# Supplemental_Power_Switch_System.net
KiCad netlist of a schematic drawn in EAGLE
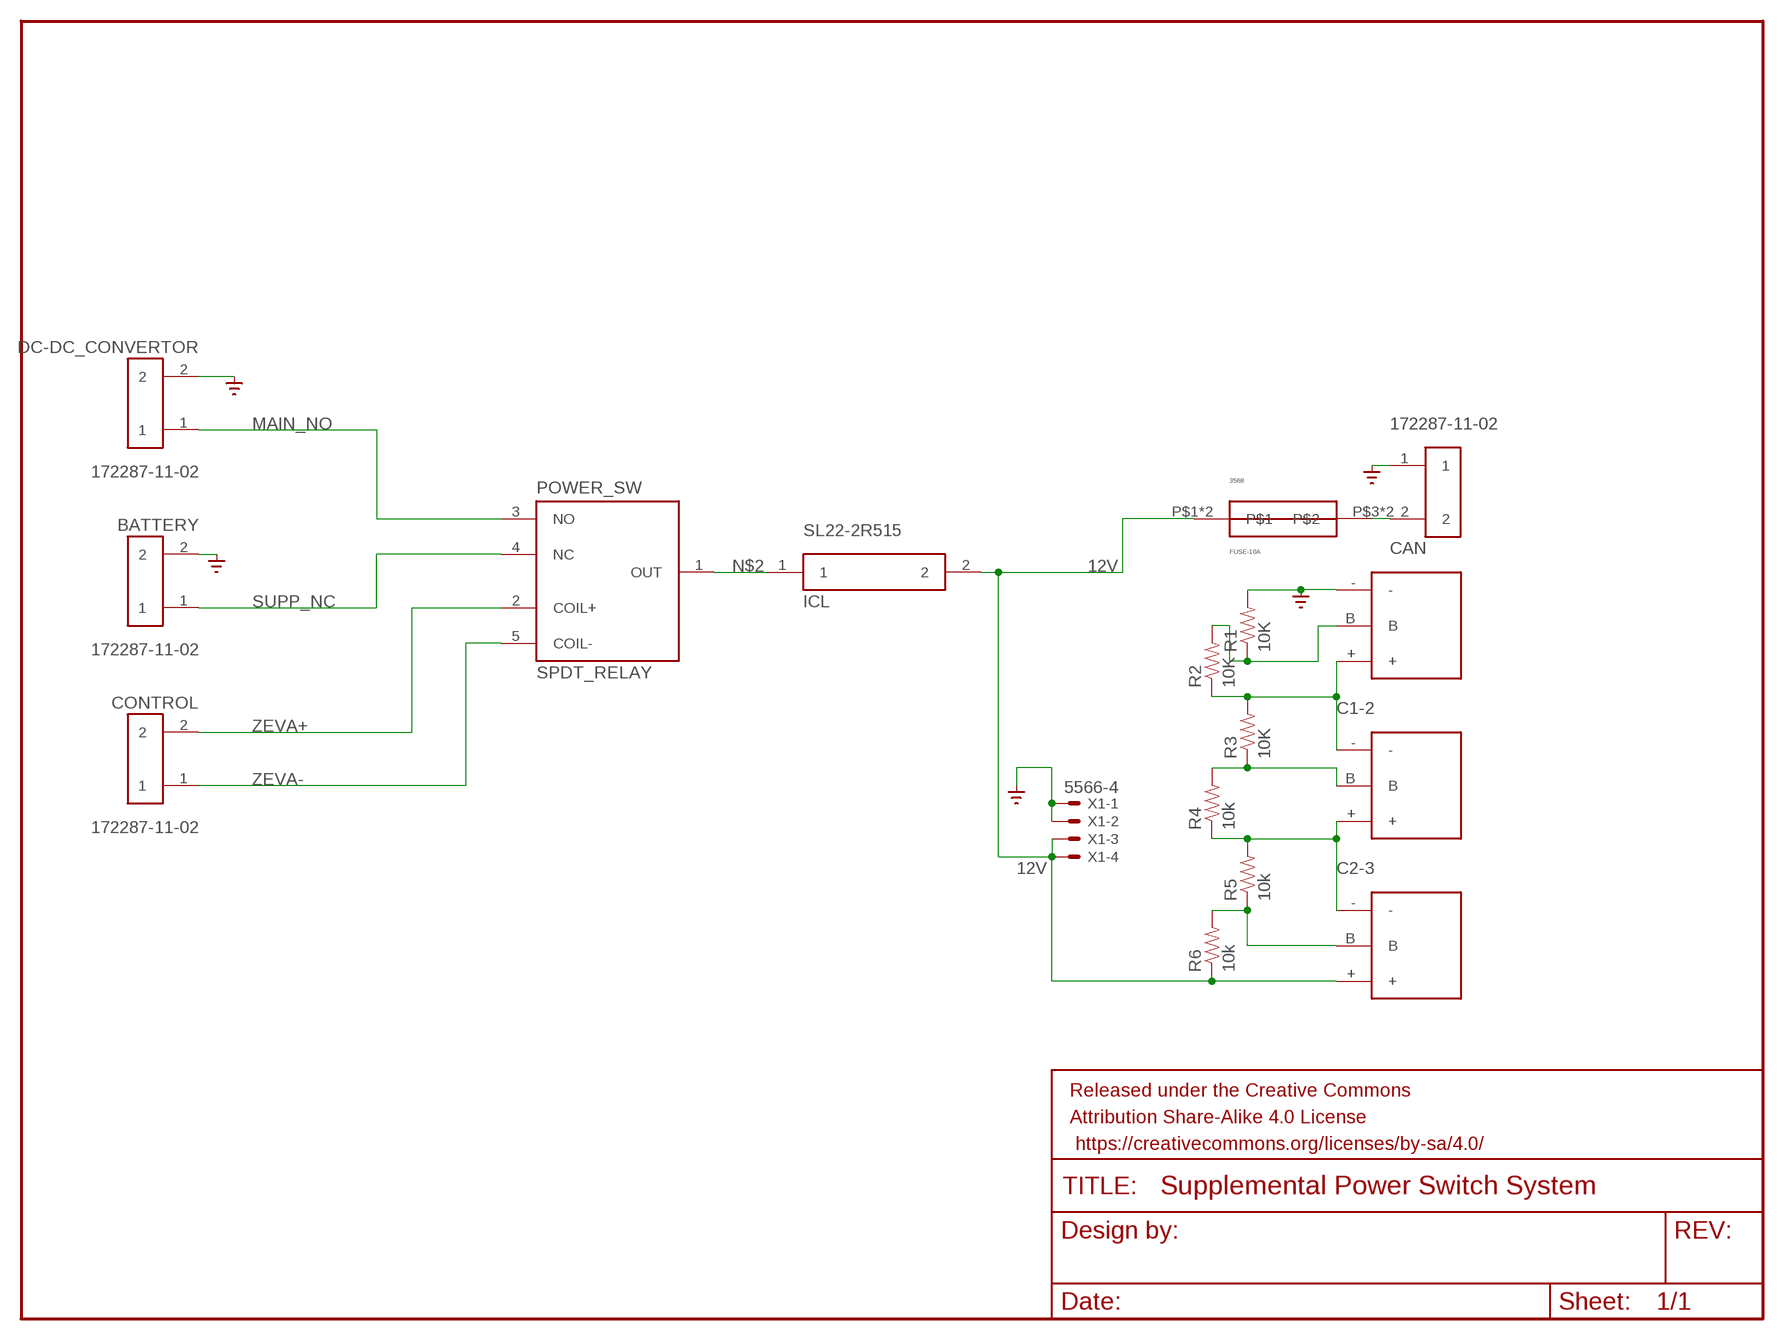
[diagram p0: schematic, sheet 1]

(export (version "E")
  (design (tool "Eeschema 10.0.6"))
  (components
    (comp (ref "BATTERY")
      (value "172287-11-02")
      (footprint "eagle-import:172287-ULTRA-FIT")
      (libsource (lib "eagle-import") (part "172287-11-02"))
    )
    (comp (ref "C1")
      (value "SUPER-CAPACITOR")
      (footprint "eagle-import:DMF")
      (libsource (lib "eagle-import") (part "SUPER-CAPACITOR"))
    )
    (comp (ref "C2")
      (value "SUPER-CAPACITOR")
      (footprint "eagle-import:DMF")
      (libsource (lib "eagle-import") (part "SUPER-CAPACITOR"))
    )
    (comp (ref "C3")
      (value "SUPER-CAPACITOR")
      (footprint "eagle-import:DMF")
      (libsource (lib "eagle-import") (part "SUPER-CAPACITOR"))
    )
    (comp (ref "CAN")
      (value "172287-11-02")
      (footprint "eagle-import:172287-ULTRA-FIT")
      (libsource (lib "eagle-import") (part "172287-11-02"))
    )
    (comp (ref "CONTROL")
      (value "172287-11-02")
      (footprint "eagle-import:172287-ULTRA-FIT")
      (libsource (lib "eagle-import") (part "172287-11-02"))
    )
    (comp (ref "DC-DC_CONVERTOR")
      (value "172287-11-02")
      (footprint "eagle-import:172287-ULTRA-FIT")
      (libsource (lib "eagle-import") (part "172287-11-02"))
    )
    (comp (ref "FRAME1")
      (value "FRAME-LETTERNO_PACKAGE")
      (footprint "eagle-import:DUMMY")
      (fields (field (name "DESIGNER") "Nobody"))
      (libsource (lib "eagle-import") (part "FRAME-LETTERNO_PACKAGE"))
    )
    (comp (ref "FUSE-10A")
      (value "3568")
      (footprint "eagle-import:3568-MINI-297")
      (libsource (lib "eagle-import") (part "3568"))
    )
    (comp (ref "ICL")
      (value "SL22-2R515")
      (footprint "eagle-import:SL22-2R515")
      (libsource (lib "eagle-import") (part "SL22-2R515"))
    )
    (comp (ref "POWER_SW")
      (value "SPDT_RELAY")
      (footprint "eagle-import:G8QN-1C4")
      (libsource (lib "eagle-import") (part "SPDT_RELAY"))
    )
    (comp (ref "R1")
      (value "10K")
      (footprint "eagle-import:1_6W-RES")
      (libsource (lib "eagle-import") (part "RESISTORPTH-1/6W"))
    )
    (comp (ref "R2")
      (value "10K")
      (footprint "eagle-import:1_6W-RES")
      (libsource (lib "eagle-import") (part "RESISTORPTH-1/6W"))
    )
    (comp (ref "R3")
      (value "10K")
      (footprint "eagle-import:1_6W-RES")
      (libsource (lib "eagle-import") (part "RESISTORPTH-1/6W"))
    )
    (comp (ref "R4")
      (value "10k")
      (footprint "eagle-import:1_6W-RES")
      (libsource (lib "eagle-import") (part "RESISTORPTH-1/6W"))
    )
    (comp (ref "R5")
      (value "10k")
      (footprint "eagle-import:1_6W-RES")
      (libsource (lib "eagle-import") (part "RESISTORPTH-1/6W"))
    )
    (comp (ref "R6")
      (value "10k")
      (footprint "eagle-import:1_6W-RES")
      (libsource (lib "eagle-import") (part "RESISTORPTH-1/6W"))
    )
    (comp (ref "X1")
      (value "5566-4")
      (footprint "eagle-import:5566-4")
      (libsource (lib "eagle-import") (part "5566-4"))
    )
  )
  (nets
    (net (code "1") (name "/12V") (class "Default")
      (node (ref "C3") (pin "+") (pinfunction "+_+") (pintype "bidirectional"))
      (node (ref "FUSE-10A") (pin "P$1") (pinfunction "P$1_P$1") (pintype "bidirectional"))
      (node (ref "FUSE-10A") (pin "P$2") (pinfunction "P$1_P$2") (pintype "bidirectional"))
      (node (ref "ICL") (pin "2") (pinfunction "2_2") (pintype "bidirectional"))
      (node (ref "R6") (pin "1") (pinfunction "1_1") (pintype "passive"))
      (node (ref "X1") (pin "3") (pinfunction "S_3") (pintype "passive"))
      (node (ref "X1") (pin "4") (pinfunction "S_4") (pintype "passive"))
    )
    (net (code "2") (name "/C1-2") (class "Default")
      (node (ref "C1") (pin "+") (pinfunction "+_+") (pintype "bidirectional"))
      (node (ref "C2") (pin "-") (pinfunction "-_-") (pintype "bidirectional"))
      (node (ref "R2") (pin "1") (pinfunction "1_1") (pintype "passive"))
      (node (ref "R3") (pin "2") (pinfunction "2_2") (pintype "passive"))
    )
    (net (code "3") (name "/C2-3") (class "Default")
      (node (ref "C2") (pin "+") (pinfunction "+_+") (pintype "bidirectional"))
      (node (ref "C3") (pin "-") (pinfunction "-_-") (pintype "bidirectional"))
      (node (ref "R4") (pin "1") (pinfunction "1_1") (pintype "passive"))
      (node (ref "R5") (pin "2") (pinfunction "2_2") (pintype "passive"))
    )
    (net (code "4") (name "/MAIN_NO") (class "Default")
      (node (ref "DC-DC_CONVERTOR") (pin "1") (pinfunction "1_1") (pintype "bidirectional"))
      (node (ref "POWER_SW") (pin "3") (pinfunction "NO_3") (pintype "input"))
    )
    (net (code "5") (name "/N$2") (class "Default")
      (node (ref "ICL") (pin "1") (pinfunction "1_1") (pintype "bidirectional"))
      (node (ref "POWER_SW") (pin "1") (pinfunction "OUT_1") (pintype "output"))
    )
    (net (code "6") (name "/SUPP_NC") (class "Default")
      (node (ref "BATTERY") (pin "1") (pinfunction "1_1") (pintype "bidirectional"))
      (node (ref "POWER_SW") (pin "4") (pinfunction "NC_4") (pintype "input"))
    )
    (net (code "7") (name "/ZEVA+") (class "Default")
      (node (ref "CONTROL") (pin "2") (pinfunction "2_2") (pintype "bidirectional"))
      (node (ref "POWER_SW") (pin "2") (pinfunction "COIL+_2") (pintype "input"))
    )
    (net (code "8") (name "/ZEVA-") (class "Default")
      (node (ref "CONTROL") (pin "1") (pinfunction "1_1") (pintype "bidirectional"))
      (node (ref "POWER_SW") (pin "5") (pinfunction "COIL-_5") (pintype "input"))
    )
    (net (code "9") (name "GND_") (class "Default")
      (node (ref "BATTERY") (pin "2") (pinfunction "2_2") (pintype "bidirectional"))
      (node (ref "C1") (pin "-") (pinfunction "-_-") (pintype "bidirectional"))
      (node (ref "CAN") (pin "1") (pinfunction "1_1") (pintype "bidirectional"))
      (node (ref "DC-DC_CONVERTOR") (pin "2") (pinfunction "2_2") (pintype "bidirectional"))
      (node (ref "R1") (pin "2") (pinfunction "2_2") (pintype "passive"))
      (node (ref "X1") (pin "1") (pinfunction "S_1") (pintype "passive"))
      (node (ref "X1") (pin "2") (pinfunction "S_2") (pintype "passive"))
    )
    (net (code "10") (name "Net-(C1-PadB)") (class "Default")
      (node (ref "C1") (pin "B") (pinfunction "B_B") (pintype "bidirectional"))
      (node (ref "R1") (pin "1") (pinfunction "1_1") (pintype "passive"))
      (node (ref "R2") (pin "2") (pinfunction "2_2") (pintype "passive"))
    )
    (net (code "11") (name "Net-(C2-PadB)") (class "Default")
      (node (ref "C2") (pin "B") (pinfunction "B_B") (pintype "bidirectional"))
      (node (ref "R3") (pin "1") (pinfunction "1_1") (pintype "passive"))
      (node (ref "R4") (pin "2") (pinfunction "2_2") (pintype "passive"))
    )
    (net (code "12") (name "Net-(C3-PadB)") (class "Default")
      (node (ref "C3") (pin "B") (pinfunction "B_B") (pintype "bidirectional"))
      (node (ref "R5") (pin "1") (pinfunction "1_1") (pintype "passive"))
      (node (ref "R6") (pin "2") (pinfunction "2_2") (pintype "passive"))
    )
    (net (code "13") (name "Net-(CAN-Pad2)") (class "Default")
      (node (ref "CAN") (pin "2") (pinfunction "2_2") (pintype "bidirectional"))
      (node (ref "FUSE-10A") (pin "P$3") (pinfunction "P$2_P$3") (pintype "bidirectional"))
      (node (ref "FUSE-10A") (pin "P$4") (pinfunction "P$2_P$4") (pintype "bidirectional"))
    )
  )
)
